# HS-736USB.net
KiCad netlist of a schematic drawn in EAGLE
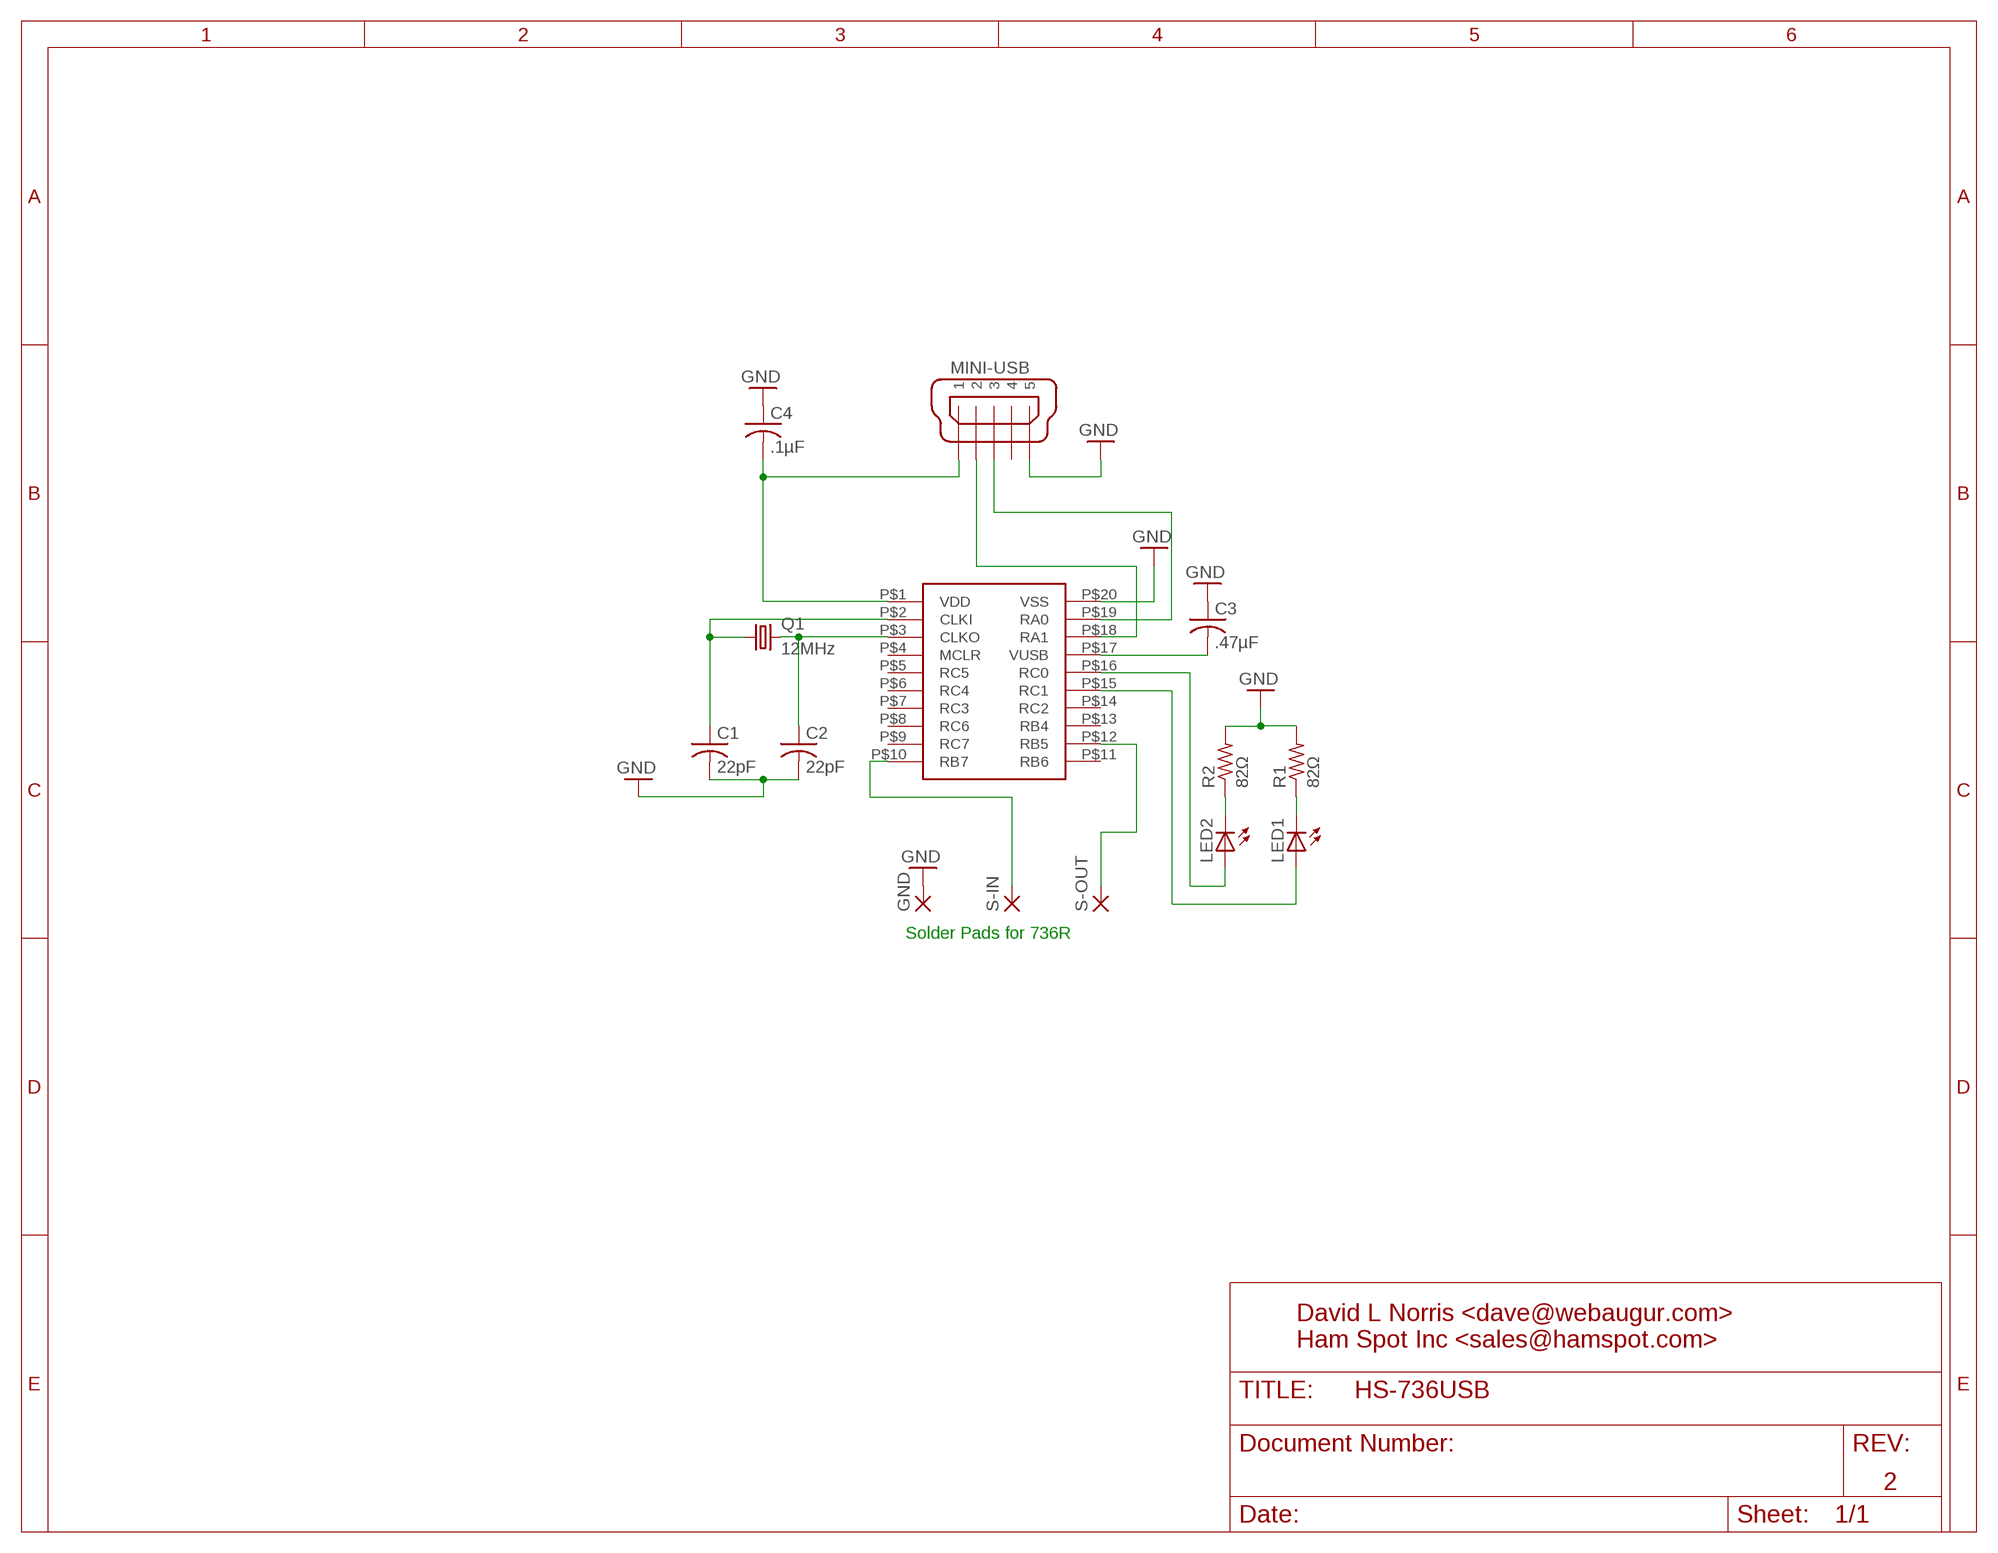
[diagram p0: schematic, sheet 1]

(export (version "E")
  (design (tool "Eeschema 10.0.6"))
  (components
    (comp (ref "C1")
      (value "22pF")
      (footprint "eagle-import:C1206")
      (libsource (lib "eagle-import") (part "C-USC1206"))
    )
    (comp (ref "C2")
      (value "22pF")
      (footprint "eagle-import:C1206")
      (libsource (lib "eagle-import") (part "C-USC1206"))
    )
    (comp (ref "C3")
      (value ".47µF")
      (footprint "eagle-import:C1206")
      (libsource (lib "eagle-import") (part "C-USC1206"))
    )
    (comp (ref "C4")
      (value ".1µF")
      (footprint "eagle-import:C1206")
      (libsource (lib "eagle-import") (part "C-USC1206"))
    )
    (comp (ref "GND")
      (value "3,17/1,3")
      (footprint "eagle-import:3,17_1,3")
      (libsource (lib "eagle-import") (part "3,17/1,3"))
    )
    (comp (ref "LED1")
      (value "LED5MM")
      (footprint "eagle-import:LED5MM")
      (libsource (lib "eagle-import") (part "LED5MM"))
    )
    (comp (ref "LED2")
      (value "LED5MM")
      (footprint "eagle-import:LED5MM")
      (libsource (lib "eagle-import") (part "LED5MM"))
    )
    (comp (ref "MINI-USB")
      (value "MINI-USB-UX60-MB-5ST")
      (footprint "eagle-import:UX60-MB-5ST")
      (libsource (lib "eagle-import") (part "MINI-USB-UX60-MB-5ST"))
    )
    (comp (ref "Q1")
      (value "12MHz")
      (footprint "eagle-import:HC49_S")
      (libsource (lib "eagle-import") (part "CRYSTALHC49S"))
    )
    (comp (ref "R1")
      (value "82Ω")
      (footprint "eagle-import:0204V")
      (libsource (lib "eagle-import") (part "R-US_0204/2V"))
    )
    (comp (ref "R2")
      (value "82Ω")
      (footprint "eagle-import:0204V")
      (libsource (lib "eagle-import") (part "R-US_0204/2V"))
    )
    (comp (ref "S-IN")
      (value "3,17/1,3")
      (footprint "eagle-import:3,17_1,3")
      (libsource (lib "eagle-import") (part "3,17/1,3"))
    )
    (comp (ref "S-OUT")
      (value "3,17/1,3")
      (footprint "eagle-import:3,17_1,3")
      (libsource (lib "eagle-import") (part "3,17/1,3"))
    )
    (comp (ref "U$1")
      (value "14K50_DIP")
      (footprint "eagle-import:14K50_DIP")
      (libsource (lib "eagle-import") (part "14K50_DIP"))
    )
  )
  (nets
    (net (code "1") (name "GND") (class "Default")
      (node (ref "C1") (pin "2") (pinfunction "2_2") (pintype "passive"))
      (node (ref "C2") (pin "2") (pinfunction "2_2") (pintype "passive"))
      (node (ref "C3") (pin "1") (pinfunction "1_1") (pintype "passive"))
      (node (ref "C4") (pin "1") (pinfunction "1_1") (pintype "passive"))
      (node (ref "GND") (pin "1") (pinfunction "P_1") (pintype "passive"))
      (node (ref "MINI-USB") (pin "5") (pinfunction "5_5") (pintype "input"))
      (node (ref "R1") (pin "2") (pinfunction "2_2") (pintype "passive"))
      (node (ref "R2") (pin "2") (pinfunction "2_2") (pintype "passive"))
      (node (ref "U$1") (pin "P$20") (pinfunction "VSS_P$20") (pintype "bidirectional"))
    )
    (net (code "2") (name "Net-(LED1-C)") (class "Default")
      (node (ref "LED1") (pin "K") (pinfunction "C_K") (pintype "passive"))
      (node (ref "R1") (pin "1") (pinfunction "1_1") (pintype "passive"))
    )
    (net (code "3") (name "Net-(LED2-C)") (class "Default")
      (node (ref "LED2") (pin "K") (pinfunction "C_K") (pintype "passive"))
      (node (ref "R2") (pin "1") (pinfunction "1_1") (pintype "passive"))
    )
    (net (code "4") (name "Net-(S-IN-P)") (class "Default")
      (node (ref "S-IN") (pin "1") (pinfunction "P_1") (pintype "passive"))
      (node (ref "U$1") (pin "P$10") (pinfunction "RB7_P$10") (pintype "bidirectional"))
    )
    (net (code "5") (name "Net-(S-OUT-P)") (class "Default")
      (node (ref "S-OUT") (pin "1") (pinfunction "P_1") (pintype "passive"))
      (node (ref "U$1") (pin "P$12") (pinfunction "RB5_P$12") (pintype "bidirectional"))
    )
    (net (code "6") (name "Net-(U$1-CLKI)") (class "Default")
      (node (ref "C1") (pin "1") (pinfunction "1_1") (pintype "passive"))
      (node (ref "Q1") (pin "1") (pinfunction "1_1") (pintype "passive"))
      (node (ref "U$1") (pin "P$2") (pinfunction "CLKI_P$2") (pintype "bidirectional"))
    )
    (net (code "7") (name "Net-(U$1-CLKO)") (class "Default")
      (node (ref "C2") (pin "1") (pinfunction "1_1") (pintype "passive"))
      (node (ref "Q1") (pin "2") (pinfunction "2_2") (pintype "passive"))
      (node (ref "U$1") (pin "P$3") (pinfunction "CLKO_P$3") (pintype "bidirectional"))
    )
    (net (code "8") (name "Net-(U$1-RA0)") (class "Default")
      (node (ref "MINI-USB") (pin "3") (pinfunction "3_3") (pintype "input"))
      (node (ref "U$1") (pin "P$19") (pinfunction "RA0_P$19") (pintype "bidirectional"))
    )
    (net (code "9") (name "Net-(U$1-RA1)") (class "Default")
      (node (ref "MINI-USB") (pin "2") (pinfunction "2_2") (pintype "input"))
      (node (ref "U$1") (pin "P$18") (pinfunction "RA1_P$18") (pintype "bidirectional"))
    )
    (net (code "10") (name "Net-(U$1-RC0)") (class "Default")
      (node (ref "LED2") (pin "A") (pinfunction "A_A") (pintype "passive"))
      (node (ref "U$1") (pin "P$16") (pinfunction "RC0_P$16") (pintype "bidirectional"))
    )
    (net (code "11") (name "Net-(U$1-RC1)") (class "Default")
      (node (ref "LED1") (pin "A") (pinfunction "A_A") (pintype "passive"))
      (node (ref "U$1") (pin "P$15") (pinfunction "RC1_P$15") (pintype "bidirectional"))
    )
    (net (code "12") (name "Net-(U$1-VDD)") (class "Default")
      (node (ref "C4") (pin "2") (pinfunction "2_2") (pintype "passive"))
      (node (ref "MINI-USB") (pin "1") (pinfunction "1_1") (pintype "input"))
      (node (ref "U$1") (pin "P$1") (pinfunction "VDD_P$1") (pintype "bidirectional"))
    )
    (net (code "13") (name "Net-(U$1-VUSB)") (class "Default")
      (node (ref "C3") (pin "2") (pinfunction "2_2") (pintype "passive"))
      (node (ref "U$1") (pin "P$17") (pinfunction "VUSB_P$17") (pintype "bidirectional"))
    )
    (net (code "14") (name "unconnected-(MINI-USB-Pad4)") (class "Default")
      (node (ref "MINI-USB") (pin "4") (pinfunction "4_4") (pintype "input"))
    )
    (net (code "15") (name "unconnected-(U$1-MCLR-PadP$4)") (class "Default")
      (node (ref "U$1") (pin "P$4") (pinfunction "MCLR_P$4") (pintype "bidirectional"))
    )
    (net (code "16") (name "unconnected-(U$1-RB4-PadP$13)") (class "Default")
      (node (ref "U$1") (pin "P$13") (pinfunction "RB4_P$13") (pintype "bidirectional"))
    )
    (net (code "17") (name "unconnected-(U$1-RB6-PadP$11)") (class "Default")
      (node (ref "U$1") (pin "P$11") (pinfunction "RB6_P$11") (pintype "bidirectional"))
    )
    (net (code "18") (name "unconnected-(U$1-RC2-PadP$14)") (class "Default")
      (node (ref "U$1") (pin "P$14") (pinfunction "RC2_P$14") (pintype "bidirectional"))
    )
    (net (code "19") (name "unconnected-(U$1-RC3-PadP$7)") (class "Default")
      (node (ref "U$1") (pin "P$7") (pinfunction "RC3_P$7") (pintype "bidirectional"))
    )
    (net (code "20") (name "unconnected-(U$1-RC4-PadP$6)") (class "Default")
      (node (ref "U$1") (pin "P$6") (pinfunction "RC4_P$6") (pintype "bidirectional"))
    )
    (net (code "21") (name "unconnected-(U$1-RC5-PadP$5)") (class "Default")
      (node (ref "U$1") (pin "P$5") (pinfunction "RC5_P$5") (pintype "bidirectional"))
    )
    (net (code "22") (name "unconnected-(U$1-RC6-PadP$8)") (class "Default")
      (node (ref "U$1") (pin "P$8") (pinfunction "RC6_P$8") (pintype "bidirectional"))
    )
    (net (code "23") (name "unconnected-(U$1-RC7-PadP$9)") (class "Default")
      (node (ref "U$1") (pin "P$9") (pinfunction "RC7_P$9") (pintype "bidirectional"))
    )
  )
)
